# ZippyTheBalancingRobot.net
KiCad netlist of a schematic drawn in EAGLE
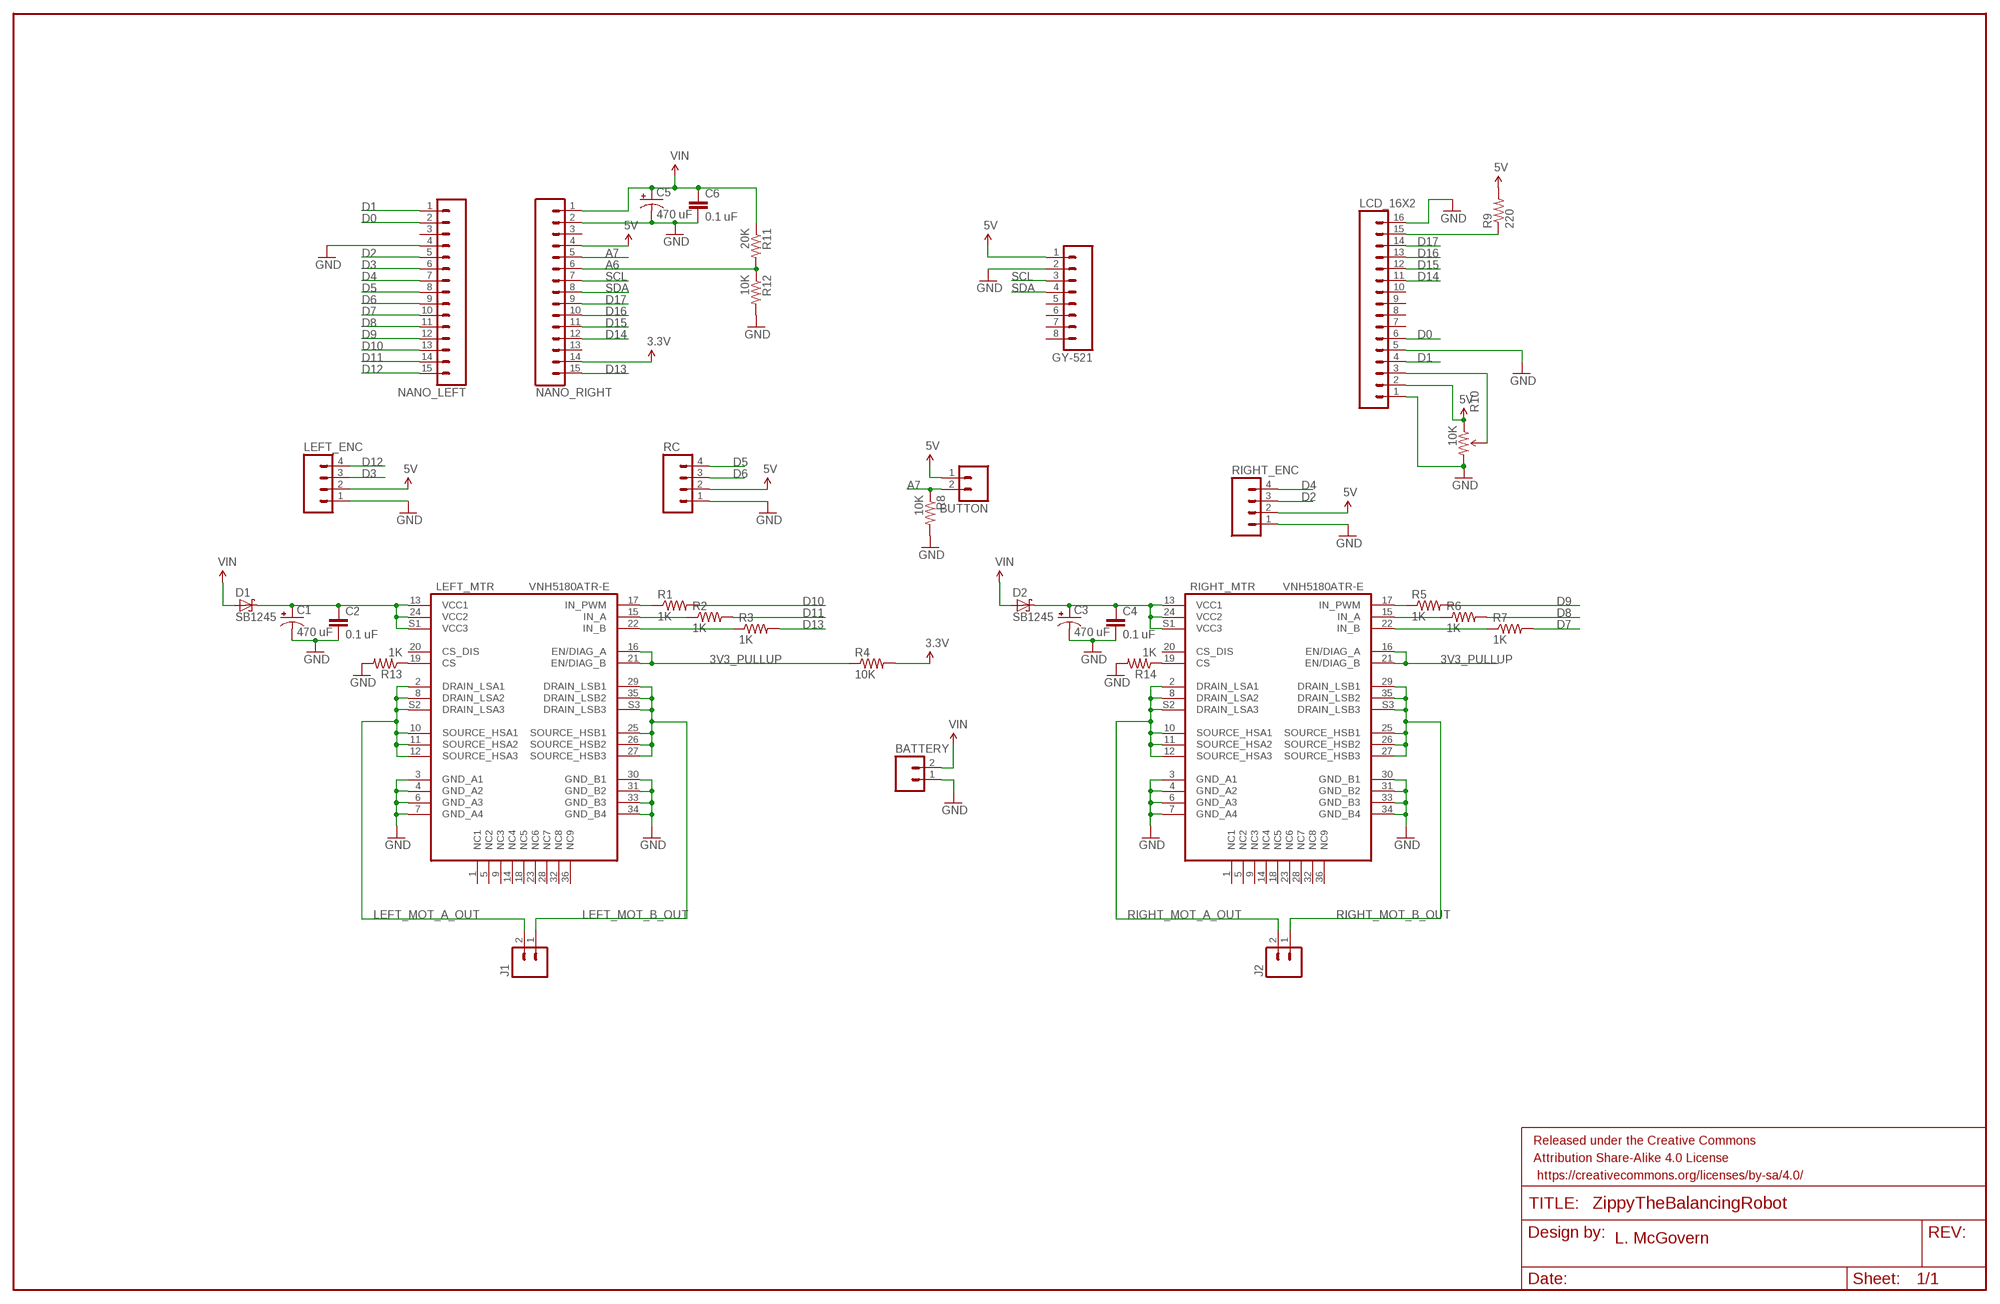
[diagram p0: schematic, sheet 1]

(export (version "E")
  (design (tool "Eeschema 10.0.6"))
  (components
    (comp (ref "BATTERY")
      (value "M025MM")
      (footprint "eagle-import:SCREWTERMINAL-5MM-2")
      (libsource (lib "eagle-import") (part "M025MM"))
    )
    (comp (ref "BUTTON")
      (value "M02PTH")
      (footprint "eagle-import:1X02")
      (libsource (lib "eagle-import") (part "M02PTH"))
    )
    (comp (ref "C1")
      (value "470 uF")
      (footprint "eagle-import:E3,5-8")
      (libsource (lib "eagle-import") (part "CPOL-USE3.5-8"))
    )
    (comp (ref "C2")
      (value "0.1 uF")
      (footprint "eagle-import:CAP-PTH-SMALL")
      (libsource (lib "eagle-import") (part "CAPPTH"))
    )
    (comp (ref "C3")
      (value "470 uF")
      (footprint "eagle-import:E3,5-8")
      (libsource (lib "eagle-import") (part "CPOL-USE3.5-8"))
    )
    (comp (ref "C4")
      (value "0.1 uF")
      (footprint "eagle-import:CAP-PTH-SMALL")
      (libsource (lib "eagle-import") (part "CAPPTH"))
    )
    (comp (ref "C5")
      (value "470 uF")
      (footprint "eagle-import:E3,5-8")
      (libsource (lib "eagle-import") (part "CPOL-USE3.5-8"))
    )
    (comp (ref "C6")
      (value "0.1 uF")
      (footprint "eagle-import:CAP-PTH-SMALL")
      (libsource (lib "eagle-import") (part "CAPPTH"))
    )
    (comp (ref "D1")
      (value "SB1245")
      (footprint "eagle-import:DO201T15")
      (libsource (lib "eagle-import") (part "SCHOTTKY-DIODEDO201T15"))
    )
    (comp (ref "D2")
      (value "SB1245")
      (footprint "eagle-import:DO201T15")
      (libsource (lib "eagle-import") (part "SCHOTTKY-DIODEDO201T15"))
    )
    (comp (ref "FRAME1")
      (value "FRAME-LEDGER")
      (footprint "eagle-import:CREATIVE_COMMONS")
      (libsource (lib "eagle-import") (part "FRAME-LEDGER"))
    )
    (comp (ref "GY-521")
      (value "M08")
      (footprint "eagle-import:1X08_ROUND")
      (libsource (lib "eagle-import") (part "M08"))
    )
    (comp (ref "J1")
      (value "M025MM")
      (footprint "eagle-import:SCREWTERMINAL-5MM-2")
      (libsource (lib "eagle-import") (part "M025MM"))
    )
    (comp (ref "J2")
      (value "M025MM")
      (footprint "eagle-import:SCREWTERMINAL-5MM-2")
      (libsource (lib "eagle-import") (part "M025MM"))
    )
    (comp (ref "LCD_16X2")
      (value "M16PTH")
      (footprint "eagle-import:1X16")
      (libsource (lib "eagle-import") (part "M16PTH"))
    )
    (comp (ref "LEFT_ENC")
      (value "M04PTH")
      (footprint "eagle-import:1X04")
      (libsource (lib "eagle-import") (part "M04PTH"))
    )
    (comp (ref "LEFT_MTR")
      (value "VNH5180ATR-E")
      (footprint "eagle-import:POWERSSO-36")
      (libsource (lib "eagle-import") (part "VNH5180ATR-E"))
    )
    (comp (ref "NANO_LEFT")
      (value "M15")
      (footprint "eagle-import:1X15")
      (libsource (lib "eagle-import") (part "M15"))
    )
    (comp (ref "NANO_RIGHT")
      (value "M15")
      (footprint "eagle-import:1X15")
      (libsource (lib "eagle-import") (part "M15"))
    )
    (comp (ref "R1")
      (value "1K")
      (footprint "eagle-import:0207_10")
      (libsource (lib "eagle-import") (part "R-US_0207/10"))
    )
    (comp (ref "R2")
      (value "1K")
      (footprint "eagle-import:0207_10")
      (libsource (lib "eagle-import") (part "R-US_0207/10"))
    )
    (comp (ref "R3")
      (value "1K")
      (footprint "eagle-import:0207_10")
      (libsource (lib "eagle-import") (part "R-US_0207/10"))
    )
    (comp (ref "R4")
      (value "10K")
      (footprint "eagle-import:0207_10")
      (libsource (lib "eagle-import") (part "R-US_0207/10"))
    )
    (comp (ref "R5")
      (value "1K")
      (footprint "eagle-import:0207_10")
      (libsource (lib "eagle-import") (part "R-US_0207/10"))
    )
    (comp (ref "R6")
      (value "1K")
      (footprint "eagle-import:0207_10")
      (libsource (lib "eagle-import") (part "R-US_0207/10"))
    )
    (comp (ref "R7")
      (value "1K")
      (footprint "eagle-import:0207_10")
      (libsource (lib "eagle-import") (part "R-US_0207/10"))
    )
    (comp (ref "R8")
      (value "10K")
      (footprint "eagle-import:0207_10")
      (libsource (lib "eagle-import") (part "R-US_0207/10"))
    )
    (comp (ref "R9")
      (value "220")
      (footprint "eagle-import:0207_10")
      (libsource (lib "eagle-import") (part "R-US_0207/10"))
    )
    (comp (ref "R10")
      (value "10K")
      (footprint "eagle-import:3386U")
      (libsource (lib "eagle-import") (part "TRIMPOT-PTH-KNOB"))
    )
    (comp (ref "R11")
      (value "20K")
      (footprint "eagle-import:0207_10")
      (libsource (lib "eagle-import") (part "R-US_0207/10"))
    )
    (comp (ref "R12")
      (value "10K")
      (footprint "eagle-import:0207_10")
      (libsource (lib "eagle-import") (part "R-US_0207/10"))
    )
    (comp (ref "R13")
      (value "1K")
      (footprint "eagle-import:0207_10")
      (libsource (lib "eagle-import") (part "R-US_0207/10"))
    )
    (comp (ref "R14")
      (value "1K")
      (footprint "eagle-import:0207_10")
      (libsource (lib "eagle-import") (part "R-US_0207/10"))
    )
    (comp (ref "RC")
      (value "M04PTH")
      (footprint "eagle-import:1X04")
      (libsource (lib "eagle-import") (part "M04PTH"))
    )
    (comp (ref "RIGHT_ENC")
      (value "M04PTH")
      (footprint "eagle-import:1X04")
      (libsource (lib "eagle-import") (part "M04PTH"))
    )
    (comp (ref "RIGHT_MTR")
      (value "VNH5180ATR-E")
      (footprint "eagle-import:POWERSSO-36")
      (libsource (lib "eagle-import") (part "VNH5180ATR-E"))
    )
  )
  (nets
    (net (code "1") (name "/3V3_PULLUP") (class "Default")
      (node (ref "LEFT_MTR") (pin "16") (pinfunction "EN/DIAG_A_16") (pintype "input"))
      (node (ref "LEFT_MTR") (pin "21") (pinfunction "EN/DIAG_B_21") (pintype "input"))
      (node (ref "R4") (pin "1") (pinfunction "1_1") (pintype "passive"))
      (node (ref "RIGHT_MTR") (pin "16") (pinfunction "EN/DIAG_A_16") (pintype "input"))
      (node (ref "RIGHT_MTR") (pin "21") (pinfunction "EN/DIAG_B_21") (pintype "input"))
    )
    (net (code "2") (name "/A6") (class "Default")
      (node (ref "NANO_RIGHT") (pin "6") (pinfunction "6_6") (pintype "passive"))
      (node (ref "R11") (pin "2") (pinfunction "2_2") (pintype "passive"))
      (node (ref "R12") (pin "1") (pinfunction "1_1") (pintype "passive"))
    )
    (net (code "3") (name "/A7") (class "Default")
      (node (ref "BUTTON") (pin "2") (pinfunction "2_2") (pintype "passive"))
      (node (ref "NANO_RIGHT") (pin "5") (pinfunction "5_5") (pintype "passive"))
      (node (ref "R8") (pin "1") (pinfunction "1_1") (pintype "passive"))
    )
    (net (code "4") (name "/D0") (class "Default")
      (node (ref "LCD_16X2") (pin "6") (pinfunction "6_6") (pintype "passive"))
      (node (ref "NANO_LEFT") (pin "2") (pinfunction "2_2") (pintype "passive"))
    )
    (net (code "5") (name "/D1") (class "Default")
      (node (ref "LCD_16X2") (pin "4") (pinfunction "4_4") (pintype "passive"))
      (node (ref "NANO_LEFT") (pin "1") (pinfunction "1_1") (pintype "passive"))
    )
    (net (code "6") (name "/D2") (class "Default")
      (node (ref "NANO_LEFT") (pin "5") (pinfunction "5_5") (pintype "passive"))
      (node (ref "RIGHT_ENC") (pin "3") (pinfunction "3_3") (pintype "passive"))
    )
    (net (code "7") (name "/D3") (class "Default")
      (node (ref "LEFT_ENC") (pin "3") (pinfunction "3_3") (pintype "passive"))
      (node (ref "NANO_LEFT") (pin "6") (pinfunction "6_6") (pintype "passive"))
    )
    (net (code "8") (name "/D4") (class "Default")
      (node (ref "NANO_LEFT") (pin "7") (pinfunction "7_7") (pintype "passive"))
      (node (ref "RIGHT_ENC") (pin "4") (pinfunction "4_4") (pintype "passive"))
    )
    (net (code "9") (name "/D5") (class "Default")
      (node (ref "NANO_LEFT") (pin "8") (pinfunction "8_8") (pintype "passive"))
      (node (ref "RC") (pin "4") (pinfunction "4_4") (pintype "passive"))
    )
    (net (code "10") (name "/D6") (class "Default")
      (node (ref "NANO_LEFT") (pin "9") (pinfunction "9_9") (pintype "passive"))
      (node (ref "RC") (pin "3") (pinfunction "3_3") (pintype "passive"))
    )
    (net (code "11") (name "/D7") (class "Default")
      (node (ref "NANO_LEFT") (pin "10") (pinfunction "10_10") (pintype "passive"))
      (node (ref "R7") (pin "2") (pinfunction "2_2") (pintype "passive"))
    )
    (net (code "12") (name "/D8") (class "Default")
      (node (ref "NANO_LEFT") (pin "11") (pinfunction "11_11") (pintype "passive"))
      (node (ref "R6") (pin "2") (pinfunction "2_2") (pintype "passive"))
    )
    (net (code "13") (name "/D9") (class "Default")
      (node (ref "NANO_LEFT") (pin "12") (pinfunction "12_12") (pintype "passive"))
      (node (ref "R5") (pin "2") (pinfunction "2_2") (pintype "passive"))
    )
    (net (code "14") (name "/D10") (class "Default")
      (node (ref "NANO_LEFT") (pin "13") (pinfunction "13_13") (pintype "passive"))
      (node (ref "R1") (pin "2") (pinfunction "2_2") (pintype "passive"))
    )
    (net (code "15") (name "/D11") (class "Default")
      (node (ref "NANO_LEFT") (pin "14") (pinfunction "14_14") (pintype "passive"))
      (node (ref "R2") (pin "2") (pinfunction "2_2") (pintype "passive"))
    )
    (net (code "16") (name "/D12") (class "Default")
      (node (ref "LEFT_ENC") (pin "4") (pinfunction "4_4") (pintype "passive"))
      (node (ref "NANO_LEFT") (pin "15") (pinfunction "15_15") (pintype "passive"))
    )
    (net (code "17") (name "/D13") (class "Default")
      (node (ref "NANO_RIGHT") (pin "15") (pinfunction "15_15") (pintype "passive"))
      (node (ref "R3") (pin "2") (pinfunction "2_2") (pintype "passive"))
    )
    (net (code "18") (name "/D14") (class "Default")
      (node (ref "LCD_16X2") (pin "11") (pinfunction "11_11") (pintype "passive"))
      (node (ref "NANO_RIGHT") (pin "12") (pinfunction "12_12") (pintype "passive"))
    )
    (net (code "19") (name "/D15") (class "Default")
      (node (ref "LCD_16X2") (pin "12") (pinfunction "12_12") (pintype "passive"))
      (node (ref "NANO_RIGHT") (pin "11") (pinfunction "11_11") (pintype "passive"))
    )
    (net (code "20") (name "/D16") (class "Default")
      (node (ref "LCD_16X2") (pin "13") (pinfunction "13_13") (pintype "passive"))
      (node (ref "NANO_RIGHT") (pin "10") (pinfunction "10_10") (pintype "passive"))
    )
    (net (code "21") (name "/D17") (class "Default")
      (node (ref "LCD_16X2") (pin "14") (pinfunction "14_14") (pintype "passive"))
      (node (ref "NANO_RIGHT") (pin "9") (pinfunction "9_9") (pintype "passive"))
    )
    (net (code "22") (name "/LEFT_MOT_A_OUT") (class "Default")
      (node (ref "J1") (pin "2") (pinfunction "2_2") (pintype "passive"))
      (node (ref "LEFT_MTR") (pin "10") (pinfunction "SOURCE_HSA1_10") (pintype "bidirectional"))
      (node (ref "LEFT_MTR") (pin "11") (pinfunction "SOURCE_HSA2_11") (pintype "bidirectional"))
      (node (ref "LEFT_MTR") (pin "12") (pinfunction "SOURCE_HSA3_12") (pintype "bidirectional"))
      (node (ref "LEFT_MTR") (pin "2") (pinfunction "DRAIN_LSA1_2") (pintype "bidirectional"))
      (node (ref "LEFT_MTR") (pin "8") (pinfunction "DRAIN_LSA2_8") (pintype "bidirectional"))
      (node (ref "LEFT_MTR") (pin "S2") (pinfunction "DRAIN_LSA3_S2") (pintype "bidirectional"))
    )
    (net (code "23") (name "/LEFT_MOT_B_OUT") (class "Default")
      (node (ref "J1") (pin "1") (pinfunction "1_1") (pintype "passive"))
      (node (ref "LEFT_MTR") (pin "25") (pinfunction "SOURCE_HSB1_25") (pintype "bidirectional"))
      (node (ref "LEFT_MTR") (pin "26") (pinfunction "SOURCE_HSB2_26") (pintype "bidirectional"))
      (node (ref "LEFT_MTR") (pin "27") (pinfunction "SOURCE_HSB3_27") (pintype "bidirectional"))
      (node (ref "LEFT_MTR") (pin "29") (pinfunction "DRAIN_LSB1_29") (pintype "bidirectional"))
      (node (ref "LEFT_MTR") (pin "35") (pinfunction "DRAIN_LSB2_35") (pintype "bidirectional"))
      (node (ref "LEFT_MTR") (pin "S3") (pinfunction "DRAIN_LSB3_S3") (pintype "bidirectional"))
    )
    (net (code "24") (name "/RIGHT_MOT_A_OUT") (class "Default")
      (node (ref "J2") (pin "2") (pinfunction "2_2") (pintype "passive"))
      (node (ref "RIGHT_MTR") (pin "10") (pinfunction "SOURCE_HSA1_10") (pintype "bidirectional"))
      (node (ref "RIGHT_MTR") (pin "11") (pinfunction "SOURCE_HSA2_11") (pintype "bidirectional"))
      (node (ref "RIGHT_MTR") (pin "12") (pinfunction "SOURCE_HSA3_12") (pintype "bidirectional"))
      (node (ref "RIGHT_MTR") (pin "2") (pinfunction "DRAIN_LSA1_2") (pintype "bidirectional"))
      (node (ref "RIGHT_MTR") (pin "8") (pinfunction "DRAIN_LSA2_8") (pintype "bidirectional"))
      (node (ref "RIGHT_MTR") (pin "S2") (pinfunction "DRAIN_LSA3_S2") (pintype "bidirectional"))
    )
    (net (code "25") (name "/RIGHT_MOT_B_OUT") (class "Default")
      (node (ref "J2") (pin "1") (pinfunction "1_1") (pintype "passive"))
      (node (ref "RIGHT_MTR") (pin "25") (pinfunction "SOURCE_HSB1_25") (pintype "bidirectional"))
      (node (ref "RIGHT_MTR") (pin "26") (pinfunction "SOURCE_HSB2_26") (pintype "bidirectional"))
      (node (ref "RIGHT_MTR") (pin "27") (pinfunction "SOURCE_HSB3_27") (pintype "bidirectional"))
      (node (ref "RIGHT_MTR") (pin "29") (pinfunction "DRAIN_LSB1_29") (pintype "bidirectional"))
      (node (ref "RIGHT_MTR") (pin "35") (pinfunction "DRAIN_LSB2_35") (pintype "bidirectional"))
      (node (ref "RIGHT_MTR") (pin "S3") (pinfunction "DRAIN_LSB3_S3") (pintype "bidirectional"))
    )
    (net (code "26") (name "/SCL") (class "Default")
      (node (ref "GY-521") (pin "3") (pinfunction "3_3") (pintype "passive"))
      (node (ref "NANO_RIGHT") (pin "7") (pinfunction "7_7") (pintype "passive"))
    )
    (net (code "27") (name "/SDA") (class "Default")
      (node (ref "GY-521") (pin "4") (pinfunction "4_4") (pintype "passive"))
      (node (ref "NANO_RIGHT") (pin "8") (pinfunction "8_8") (pintype "passive"))
    )
    (net (code "28") (name "3.3V") (class "Default")
      (node (ref "NANO_RIGHT") (pin "14") (pinfunction "14_14") (pintype "passive"))
      (node (ref "R4") (pin "2") (pinfunction "2_2") (pintype "passive"))
    )
    (net (code "29") (name "5V") (class "Default")
      (node (ref "BUTTON") (pin "1") (pinfunction "1_1") (pintype "passive"))
      (node (ref "GY-521") (pin "1") (pinfunction "1_1") (pintype "passive"))
      (node (ref "LCD_16X2") (pin "2") (pinfunction "2_2") (pintype "passive"))
      (node (ref "LEFT_ENC") (pin "2") (pinfunction "2_2") (pintype "passive"))
      (node (ref "NANO_RIGHT") (pin "4") (pinfunction "4_4") (pintype "passive"))
      (node (ref "R10") (pin "1") (pinfunction "CCW_1") (pintype "passive"))
      (node (ref "R9") (pin "2") (pinfunction "2_2") (pintype "passive"))
      (node (ref "RC") (pin "2") (pinfunction "2_2") (pintype "passive"))
      (node (ref "RIGHT_ENC") (pin "2") (pinfunction "2_2") (pintype "passive"))
    )
    (net (code "30") (name "GND") (class "Default")
      (node (ref "BATTERY") (pin "1") (pinfunction "1_1") (pintype "passive"))
      (node (ref "C1") (pin "-") (pinfunction "-_-") (pintype "passive"))
      (node (ref "C2") (pin "2") (pinfunction "2_2") (pintype "passive"))
      (node (ref "C3") (pin "-") (pinfunction "-_-") (pintype "passive"))
      (node (ref "C4") (pin "2") (pinfunction "2_2") (pintype "passive"))
      (node (ref "C5") (pin "-") (pinfunction "-_-") (pintype "passive"))
      (node (ref "C6") (pin "2") (pinfunction "2_2") (pintype "passive"))
      (node (ref "GY-521") (pin "2") (pinfunction "2_2") (pintype "passive"))
      (node (ref "LCD_16X2") (pin "1") (pinfunction "1_1") (pintype "passive"))
      (node (ref "LCD_16X2") (pin "16") (pinfunction "16_16") (pintype "passive"))
      (node (ref "LCD_16X2") (pin "5") (pinfunction "5_5") (pintype "passive"))
      (node (ref "LEFT_ENC") (pin "1") (pinfunction "1_1") (pintype "passive"))
      (node (ref "LEFT_MTR") (pin "3") (pinfunction "GND_A1_3") (pintype "power_in"))
      (node (ref "LEFT_MTR") (pin "30") (pinfunction "GND_B1_30") (pintype "power_in"))
      (node (ref "LEFT_MTR") (pin "31") (pinfunction "GND_B2_31") (pintype "power_in"))
      (node (ref "LEFT_MTR") (pin "33") (pinfunction "GND_B3_33") (pintype "power_in"))
      (node (ref "LEFT_MTR") (pin "34") (pinfunction "GND_B4_34") (pintype "power_in"))
      (node (ref "LEFT_MTR") (pin "4") (pinfunction "GND_A2_4") (pintype "power_in"))
      (node (ref "LEFT_MTR") (pin "6") (pinfunction "GND_A3_6") (pintype "power_in"))
      (node (ref "LEFT_MTR") (pin "7") (pinfunction "GND_A4_7") (pintype "power_in"))
      (node (ref "NANO_LEFT") (pin "4") (pinfunction "4_4") (pintype "passive"))
      (node (ref "NANO_RIGHT") (pin "2") (pinfunction "2_2") (pintype "passive"))
      (node (ref "R10") (pin "3") (pinfunction "CW_3") (pintype "passive"))
      (node (ref "R12") (pin "2") (pinfunction "2_2") (pintype "passive"))
      (node (ref "R13") (pin "2") (pinfunction "2_2") (pintype "passive"))
      (node (ref "R14") (pin "2") (pinfunction "2_2") (pintype "passive"))
      (node (ref "R8") (pin "2") (pinfunction "2_2") (pintype "passive"))
      (node (ref "RC") (pin "1") (pinfunction "1_1") (pintype "passive"))
      (node (ref "RIGHT_ENC") (pin "1") (pinfunction "1_1") (pintype "passive"))
      (node (ref "RIGHT_MTR") (pin "3") (pinfunction "GND_A1_3") (pintype "power_in"))
      (node (ref "RIGHT_MTR") (pin "30") (pinfunction "GND_B1_30") (pintype "power_in"))
      (node (ref "RIGHT_MTR") (pin "31") (pinfunction "GND_B2_31") (pintype "power_in"))
      (node (ref "RIGHT_MTR") (pin "33") (pinfunction "GND_B3_33") (pintype "power_in"))
      (node (ref "RIGHT_MTR") (pin "34") (pinfunction "GND_B4_34") (pintype "power_in"))
      (node (ref "RIGHT_MTR") (pin "4") (pinfunction "GND_A2_4") (pintype "power_in"))
      (node (ref "RIGHT_MTR") (pin "6") (pinfunction "GND_A3_6") (pintype "power_in"))
      (node (ref "RIGHT_MTR") (pin "7") (pinfunction "GND_A4_7") (pintype "power_in"))
    )
    (net (code "31") (name "Net-(LCD_16X2-Pad15)") (class "Default")
      (node (ref "LCD_16X2") (pin "15") (pinfunction "15_15") (pintype "passive"))
      (node (ref "R9") (pin "1") (pinfunction "1_1") (pintype "passive"))
    )
    (net (code "32") (name "Net-(LEFT_MTR-CS)") (class "Default")
      (node (ref "LEFT_MTR") (pin "19") (pinfunction "CS_19") (pintype "output"))
      (node (ref "R13") (pin "1") (pinfunction "1_1") (pintype "passive"))
    )
    (net (code "33") (name "Net-(LEFT_MTR-IN_A)") (class "Default")
      (node (ref "LEFT_MTR") (pin "15") (pinfunction "IN_A_15") (pintype "input"))
      (node (ref "R2") (pin "1") (pinfunction "1_1") (pintype "passive"))
    )
    (net (code "34") (name "Net-(LEFT_MTR-IN_B)") (class "Default")
      (node (ref "LEFT_MTR") (pin "22") (pinfunction "IN_B_22") (pintype "input"))
      (node (ref "R3") (pin "1") (pinfunction "1_1") (pintype "passive"))
    )
    (net (code "35") (name "Net-(LEFT_MTR-IN_PWM)") (class "Default")
      (node (ref "LEFT_MTR") (pin "17") (pinfunction "IN_PWM_17") (pintype "input"))
      (node (ref "R1") (pin "1") (pinfunction "1_1") (pintype "passive"))
    )
    (net (code "36") (name "Net-(LEFT_MTR-VCC1)") (class "Default")
      (node (ref "C1") (pin "+") (pinfunction "+_+") (pintype "passive"))
      (node (ref "C2") (pin "1") (pinfunction "1_1") (pintype "passive"))
      (node (ref "D1") (pin "C") (pinfunction "C_C") (pintype "passive"))
      (node (ref "LEFT_MTR") (pin "13") (pinfunction "VCC1_13") (pintype "power_in"))
      (node (ref "LEFT_MTR") (pin "24") (pinfunction "VCC2_24") (pintype "power_in"))
      (node (ref "LEFT_MTR") (pin "S1") (pinfunction "VCC3_S1") (pintype "power_in"))
    )
    (net (code "37") (name "Net-(R10-WIPER)") (class "Default")
      (node (ref "LCD_16X2") (pin "3") (pinfunction "3_3") (pintype "passive"))
      (node (ref "R10") (pin "2") (pinfunction "WIPER_2") (pintype "passive"))
    )
    (net (code "38") (name "Net-(RIGHT_MTR-CS)") (class "Default")
      (node (ref "R14") (pin "1") (pinfunction "1_1") (pintype "passive"))
      (node (ref "RIGHT_MTR") (pin "19") (pinfunction "CS_19") (pintype "output"))
    )
    (net (code "39") (name "Net-(RIGHT_MTR-IN_A)") (class "Default")
      (node (ref "R6") (pin "1") (pinfunction "1_1") (pintype "passive"))
      (node (ref "RIGHT_MTR") (pin "15") (pinfunction "IN_A_15") (pintype "input"))
    )
    (net (code "40") (name "Net-(RIGHT_MTR-IN_B)") (class "Default")
      (node (ref "R7") (pin "1") (pinfunction "1_1") (pintype "passive"))
      (node (ref "RIGHT_MTR") (pin "22") (pinfunction "IN_B_22") (pintype "input"))
    )
    (net (code "41") (name "Net-(RIGHT_MTR-IN_PWM)") (class "Default")
      (node (ref "R5") (pin "1") (pinfunction "1_1") (pintype "passive"))
      (node (ref "RIGHT_MTR") (pin "17") (pinfunction "IN_PWM_17") (pintype "input"))
    )
    (net (code "42") (name "Net-(RIGHT_MTR-VCC1)") (class "Default")
      (node (ref "C3") (pin "+") (pinfunction "+_+") (pintype "passive"))
      (node (ref "C4") (pin "1") (pinfunction "1_1") (pintype "passive"))
      (node (ref "D2") (pin "C") (pinfunction "C_C") (pintype "passive"))
      (node (ref "RIGHT_MTR") (pin "13") (pinfunction "VCC1_13") (pintype "power_in"))
      (node (ref "RIGHT_MTR") (pin "24") (pinfunction "VCC2_24") (pintype "power_in"))
      (node (ref "RIGHT_MTR") (pin "S1") (pinfunction "VCC3_S1") (pintype "power_in"))
    )
    (net (code "43") (name "VIN") (class "Default")
      (node (ref "BATTERY") (pin "2") (pinfunction "2_2") (pintype "passive"))
      (node (ref "C5") (pin "+") (pinfunction "+_+") (pintype "passive"))
      (node (ref "C6") (pin "1") (pinfunction "1_1") (pintype "passive"))
      (node (ref "D1") (pin "A") (pinfunction "A_A") (pintype "passive"))
      (node (ref "D2") (pin "A") (pinfunction "A_A") (pintype "passive"))
      (node (ref "NANO_RIGHT") (pin "1") (pinfunction "1_1") (pintype "passive"))
      (node (ref "R11") (pin "1") (pinfunction "1_1") (pintype "passive"))
    )
    (net (code "44") (name "unconnected-(GY-521-Pad5)") (class "Default")
      (node (ref "GY-521") (pin "5") (pinfunction "5_5") (pintype "passive"))
    )
    (net (code "45") (name "unconnected-(GY-521-Pad6)") (class "Default")
      (node (ref "GY-521") (pin "6") (pinfunction "6_6") (pintype "passive"))
    )
    (net (code "46") (name "unconnected-(GY-521-Pad7)") (class "Default")
      (node (ref "GY-521") (pin "7") (pinfunction "7_7") (pintype "passive"))
    )
    (net (code "47") (name "unconnected-(GY-521-Pad8)") (class "Default")
      (node (ref "GY-521") (pin "8") (pinfunction "8_8") (pintype "passive"))
    )
    (net (code "48") (name "unconnected-(LCD_16X2-Pad7)") (class "Default")
      (node (ref "LCD_16X2") (pin "7") (pinfunction "7_7") (pintype "passive"))
    )
    (net (code "49") (name "unconnected-(LCD_16X2-Pad8)") (class "Default")
      (node (ref "LCD_16X2") (pin "8") (pinfunction "8_8") (pintype "passive"))
    )
    (net (code "50") (name "unconnected-(LCD_16X2-Pad9)") (class "Default")
      (node (ref "LCD_16X2") (pin "9") (pinfunction "9_9") (pintype "passive"))
    )
    (net (code "51") (name "unconnected-(LCD_16X2-Pad10)") (class "Default")
      (node (ref "LCD_16X2") (pin "10") (pinfunction "10_10") (pintype "passive"))
    )
    (net (code "52") (name "unconnected-(LEFT_MTR-CS_DIS-Pad20)") (class "Default")
      (node (ref "LEFT_MTR") (pin "20") (pinfunction "CS_DIS_20") (pintype "input"))
    )
    (net (code "53") (name "unconnected-(LEFT_MTR-NC1-Pad1)") (class "Default")
      (node (ref "LEFT_MTR") (pin "1") (pinfunction "NC1_1") (pintype "no_connect"))
    )
    (net (code "54") (name "unconnected-(LEFT_MTR-NC2-Pad5)") (class "Default")
      (node (ref "LEFT_MTR") (pin "5") (pinfunction "NC2_5") (pintype "no_connect"))
    )
    (net (code "55") (name "unconnected-(LEFT_MTR-NC3-Pad9)") (class "Default")
      (node (ref "LEFT_MTR") (pin "9") (pinfunction "NC3_9") (pintype "no_connect"))
    )
    (net (code "56") (name "unconnected-(LEFT_MTR-NC4-Pad14)") (class "Default")
      (node (ref "LEFT_MTR") (pin "14") (pinfunction "NC4_14") (pintype "no_connect"))
    )
    (net (code "57") (name "unconnected-(LEFT_MTR-NC5-Pad18)") (class "Default")
      (node (ref "LEFT_MTR") (pin "18") (pinfunction "NC5_18") (pintype "no_connect"))
    )
    (net (code "58") (name "unconnected-(LEFT_MTR-NC6-Pad23)") (class "Default")
      (node (ref "LEFT_MTR") (pin "23") (pinfunction "NC6_23") (pintype "no_connect"))
    )
    (net (code "59") (name "unconnected-(LEFT_MTR-NC7-Pad28)") (class "Default")
      (node (ref "LEFT_MTR") (pin "28") (pinfunction "NC7_28") (pintype "no_connect"))
    )
    (net (code "60") (name "unconnected-(LEFT_MTR-NC8-Pad32)") (class "Default")
      (node (ref "LEFT_MTR") (pin "32") (pinfunction "NC8_32") (pintype "no_connect"))
    )
    (net (code "61") (name "unconnected-(LEFT_MTR-NC9-Pad36)") (class "Default")
      (node (ref "LEFT_MTR") (pin "36") (pinfunction "NC9_36") (pintype "no_connect"))
    )
    (net (code "62") (name "unconnected-(NANO_LEFT-Pad3)") (class "Default")
      (node (ref "NANO_LEFT") (pin "3") (pinfunction "3_3") (pintype "passive"))
    )
    (net (code "63") (name "unconnected-(NANO_RIGHT-Pad3)") (class "Default")
      (node (ref "NANO_RIGHT") (pin "3") (pinfunction "3_3") (pintype "passive"))
    )
    (net (code "64") (name "unconnected-(NANO_RIGHT-Pad13)") (class "Default")
      (node (ref "NANO_RIGHT") (pin "13") (pinfunction "13_13") (pintype "passive"))
    )
    (net (code "65") (name "unconnected-(RIGHT_MTR-CS_DIS-Pad20)") (class "Default")
      (node (ref "RIGHT_MTR") (pin "20") (pinfunction "CS_DIS_20") (pintype "input"))
    )
    (net (code "66") (name "unconnected-(RIGHT_MTR-NC1-Pad1)") (class "Default")
      (node (ref "RIGHT_MTR") (pin "1") (pinfunction "NC1_1") (pintype "no_connect"))
    )
    (net (code "67") (name "unconnected-(RIGHT_MTR-NC2-Pad5)") (class "Default")
      (node (ref "RIGHT_MTR") (pin "5") (pinfunction "NC2_5") (pintype "no_connect"))
    )
    (net (code "68") (name "unconnected-(RIGHT_MTR-NC3-Pad9)") (class "Default")
      (node (ref "RIGHT_MTR") (pin "9") (pinfunction "NC3_9") (pintype "no_connect"))
    )
    (net (code "69") (name "unconnected-(RIGHT_MTR-NC4-Pad14)") (class "Default")
      (node (ref "RIGHT_MTR") (pin "14") (pinfunction "NC4_14") (pintype "no_connect"))
    )
    (net (code "70") (name "unconnected-(RIGHT_MTR-NC5-Pad18)") (class "Default")
      (node (ref "RIGHT_MTR") (pin "18") (pinfunction "NC5_18") (pintype "no_connect"))
    )
    (net (code "71") (name "unconnected-(RIGHT_MTR-NC6-Pad23)") (class "Default")
      (node (ref "RIGHT_MTR") (pin "23") (pinfunction "NC6_23") (pintype "no_connect"))
    )
    (net (code "72") (name "unconnected-(RIGHT_MTR-NC7-Pad28)") (class "Default")
      (node (ref "RIGHT_MTR") (pin "28") (pinfunction "NC7_28") (pintype "no_connect"))
    )
    (net (code "73") (name "unconnected-(RIGHT_MTR-NC8-Pad32)") (class "Default")
      (node (ref "RIGHT_MTR") (pin "32") (pinfunction "NC8_32") (pintype "no_connect"))
    )
    (net (code "74") (name "unconnected-(RIGHT_MTR-NC9-Pad36)") (class "Default")
      (node (ref "RIGHT_MTR") (pin "36") (pinfunction "NC9_36") (pintype "no_connect"))
    )
  )
)
